# slenduino_0_8_smd.net
KiCad netlist of a schematic drawn in EAGLE
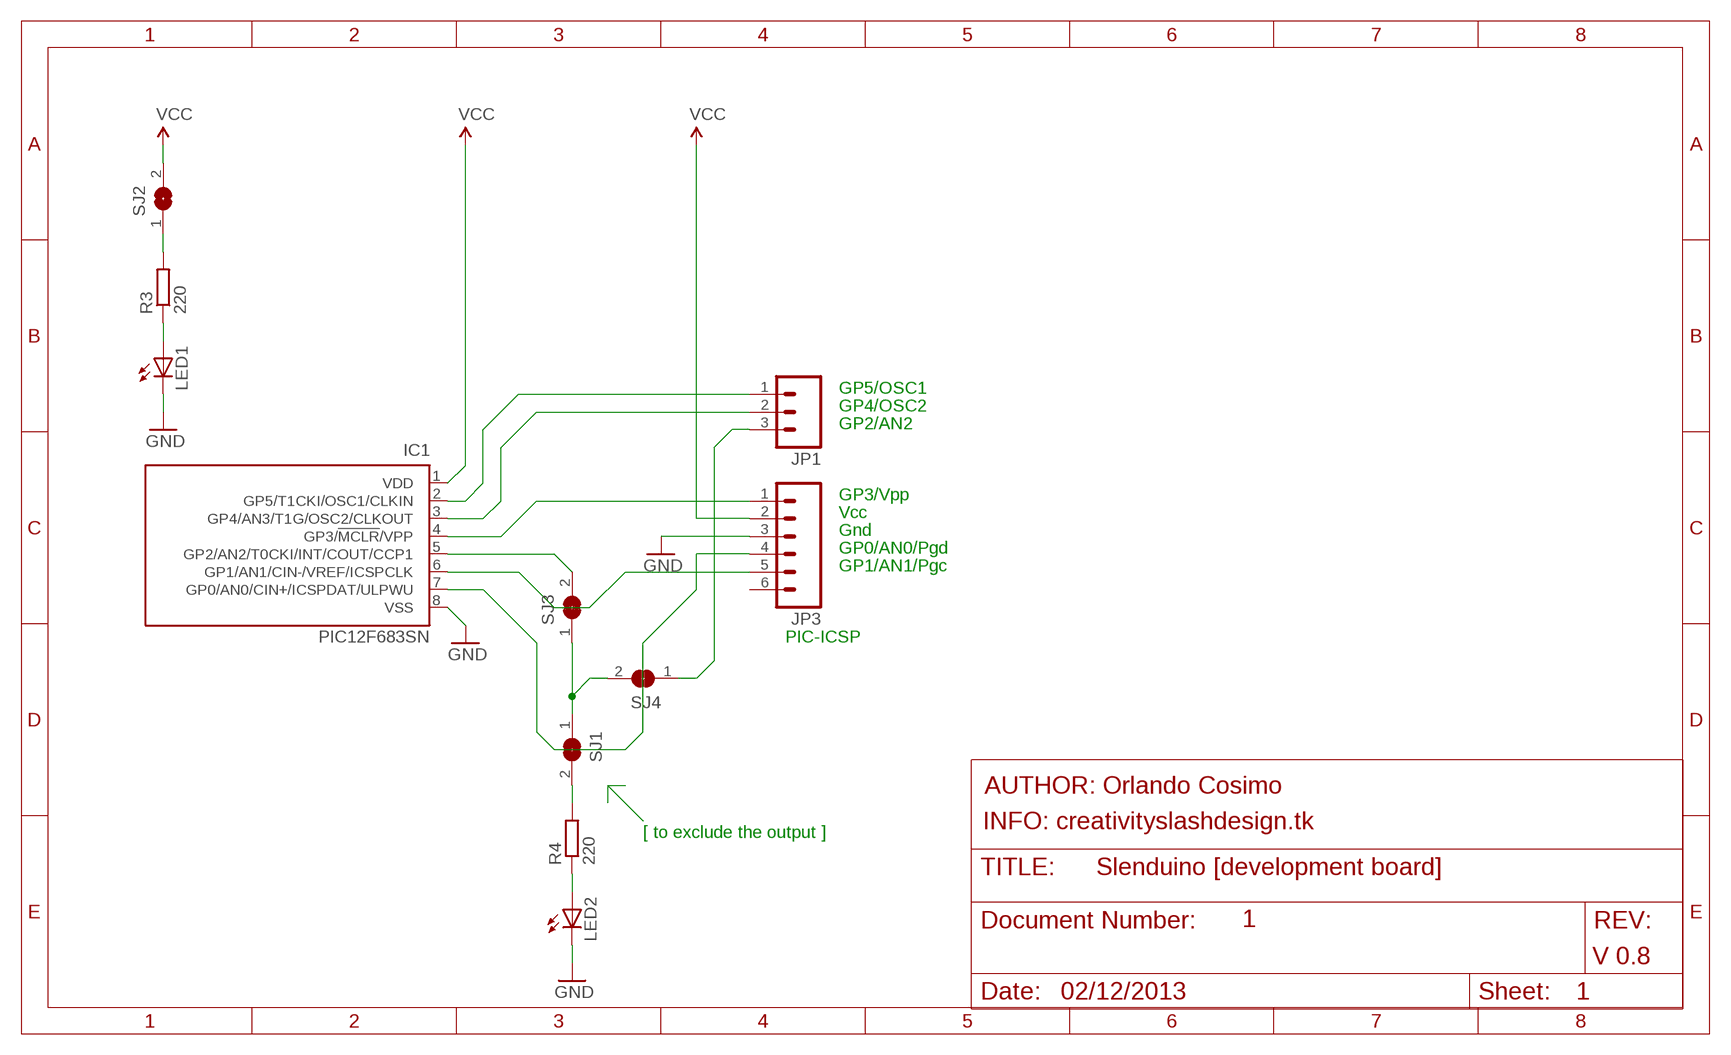
[diagram p0: schematic, sheet 1]

(export (version "E")
  (design (tool "Eeschema 10.0.6"))
  (components
    (comp (ref "IC1")
      (value "PIC12F683SN")
      (footprint "eagle-import:SO-08")
      (libsource (lib "eagle-import") (part "PIC12F683SN"))
    )
    (comp (ref "JP1")
      (value "M03LOCK_LONGPADS")
      (footprint "eagle-import:1X03_LOCK_LONGPADS")
      (libsource (lib "eagle-import") (part "M03LOCK_LONGPADS"))
    )
    (comp (ref "JP3")
      (value "M06LOCK_LONGPADS")
      (footprint "eagle-import:1X06_LOCK_LONGPADS")
      (libsource (lib "eagle-import") (part "M06LOCK_LONGPADS"))
    )
    (comp (ref "LED1")
      (value "LEDCHIPLED_0805")
      (footprint "eagle-import:CHIPLED_0805")
      (libsource (lib "eagle-import") (part "LEDCHIPLED_0805"))
    )
    (comp (ref "LED2")
      (value "LEDCHIPLED_0805")
      (footprint "eagle-import:CHIPLED_0805")
      (libsource (lib "eagle-import") (part "LEDCHIPLED_0805"))
    )
    (comp (ref "R3")
      (value "220")
      (footprint "eagle-import:M1406")
      (libsource (lib "eagle-import") (part "R-EU_M1406"))
    )
    (comp (ref "R4")
      (value "220")
      (footprint "eagle-import:M1406")
      (libsource (lib "eagle-import") (part "R-EU_M1406"))
    )
    (comp (ref "SJ1")
      (value "SJW")
      (footprint "eagle-import:SJW")
      (libsource (lib "eagle-import") (part "SJW"))
    )
    (comp (ref "SJ2")
      (value "SJW")
      (footprint "eagle-import:SJW")
      (libsource (lib "eagle-import") (part "SJW"))
    )
    (comp (ref "SJ3")
      (value "SJW")
      (footprint "eagle-import:SJW")
      (libsource (lib "eagle-import") (part "SJW"))
    )
    (comp (ref "SJ4")
      (value "SJW")
      (footprint "eagle-import:SJW")
      (libsource (lib "eagle-import") (part "SJW"))
    )
  )
  (nets
    (net (code "1") (name "GND") (class "Default")
      (node (ref "IC1") (pin "8") (pinfunction "VSS_8") (pintype "power_in"))
      (node (ref "JP3") (pin "3") (pinfunction "3_3") (pintype "passive"))
      (node (ref "LED1") (pin "C") (pinfunction "C_C") (pintype "passive"))
      (node (ref "LED2") (pin "C") (pinfunction "C_C") (pintype "passive"))
    )
    (net (code "2") (name "Net-(IC1-GP0{slash}AN0{slash}CIN+{slash}ICSPDAT{slash}ULPWU)") (class "Default")
      (node (ref "IC1") (pin "7") (pinfunction "GP0/AN0/CIN+/ICSPDAT/ULPWU_7") (pintype "bidirectional"))
      (node (ref "JP3") (pin "4") (pinfunction "4_4") (pintype "passive"))
    )
    (net (code "3") (name "Net-(IC1-GP1{slash}AN1{slash}CIN-{slash}VREF{slash}ICSPCLK)") (class "Default")
      (node (ref "IC1") (pin "6") (pinfunction "GP1/AN1/CIN-/VREF/ICSPCLK_6") (pintype "bidirectional"))
      (node (ref "JP3") (pin "5") (pinfunction "5_5") (pintype "passive"))
    )
    (net (code "4") (name "Net-(IC1-GP2{slash}AN2{slash}T0CKI{slash}INT{slash}COUT{slash}CCP1)") (class "Default")
      (node (ref "IC1") (pin "5") (pinfunction "GP2/AN2/T0CKI/INT/COUT/CCP1_5") (pintype "bidirectional"))
      (node (ref "SJ3") (pin "2") (pinfunction "2_2") (pintype "passive"))
    )
    (net (code "5") (name "Net-(IC1-GP3{slash}~{MCLR}{slash}VPP)") (class "Default")
      (node (ref "IC1") (pin "4") (pinfunction "GP3/~{MCLR}/VPP_4") (pintype "bidirectional"))
      (node (ref "JP3") (pin "1") (pinfunction "1_1") (pintype "passive"))
    )
    (net (code "6") (name "Net-(IC1-GP4{slash}AN3{slash}T1G{slash}OSC2{slash}CLKOUT)") (class "Default")
      (node (ref "IC1") (pin "3") (pinfunction "GP4/AN3/T1G/OSC2/CLKOUT_3") (pintype "bidirectional"))
      (node (ref "JP1") (pin "2") (pinfunction "2_2") (pintype "passive"))
    )
    (net (code "7") (name "Net-(IC1-GP5{slash}T1CKI{slash}OSC1{slash}CLKIN)") (class "Default")
      (node (ref "IC1") (pin "2") (pinfunction "GP5/T1CKI/OSC1/CLKIN_2") (pintype "bidirectional"))
      (node (ref "JP1") (pin "1") (pinfunction "1_1") (pintype "passive"))
    )
    (net (code "8") (name "Net-(JP1-Pad3)") (class "Default")
      (node (ref "JP1") (pin "3") (pinfunction "3_3") (pintype "passive"))
      (node (ref "SJ4") (pin "1") (pinfunction "1_1") (pintype "passive"))
    )
    (net (code "9") (name "Net-(LED1-PadA)") (class "Default")
      (node (ref "LED1") (pin "A") (pinfunction "A_A") (pintype "passive"))
      (node (ref "R3") (pin "1") (pinfunction "1_1") (pintype "passive"))
    )
    (net (code "10") (name "Net-(LED2-PadA)") (class "Default")
      (node (ref "LED2") (pin "A") (pinfunction "A_A") (pintype "passive"))
      (node (ref "R4") (pin "1") (pinfunction "1_1") (pintype "passive"))
    )
    (net (code "11") (name "Net-(R3-Pad2)") (class "Default")
      (node (ref "R3") (pin "2") (pinfunction "2_2") (pintype "passive"))
      (node (ref "SJ2") (pin "1") (pinfunction "1_1") (pintype "passive"))
    )
    (net (code "12") (name "Net-(R4-Pad2)") (class "Default")
      (node (ref "R4") (pin "2") (pinfunction "2_2") (pintype "passive"))
      (node (ref "SJ1") (pin "2") (pinfunction "2_2") (pintype "passive"))
    )
    (net (code "13") (name "Net-(SJ1-Pad1)") (class "Default")
      (node (ref "SJ1") (pin "1") (pinfunction "1_1") (pintype "passive"))
      (node (ref "SJ3") (pin "1") (pinfunction "1_1") (pintype "passive"))
      (node (ref "SJ4") (pin "2") (pinfunction "2_2") (pintype "passive"))
    )
    (net (code "14") (name "VCC") (class "Default")
      (node (ref "IC1") (pin "1") (pinfunction "VDD_1") (pintype "power_in"))
      (node (ref "JP3") (pin "2") (pinfunction "2_2") (pintype "passive"))
      (node (ref "SJ2") (pin "2") (pinfunction "2_2") (pintype "passive"))
    )
    (net (code "15") (name "unconnected-(JP3-Pad6)") (class "Default")
      (node (ref "JP3") (pin "6") (pinfunction "6_6") (pintype "passive"))
    )
  )
)
